# probe_v2.net
KiCad netlist of a schematic drawn in EAGLE
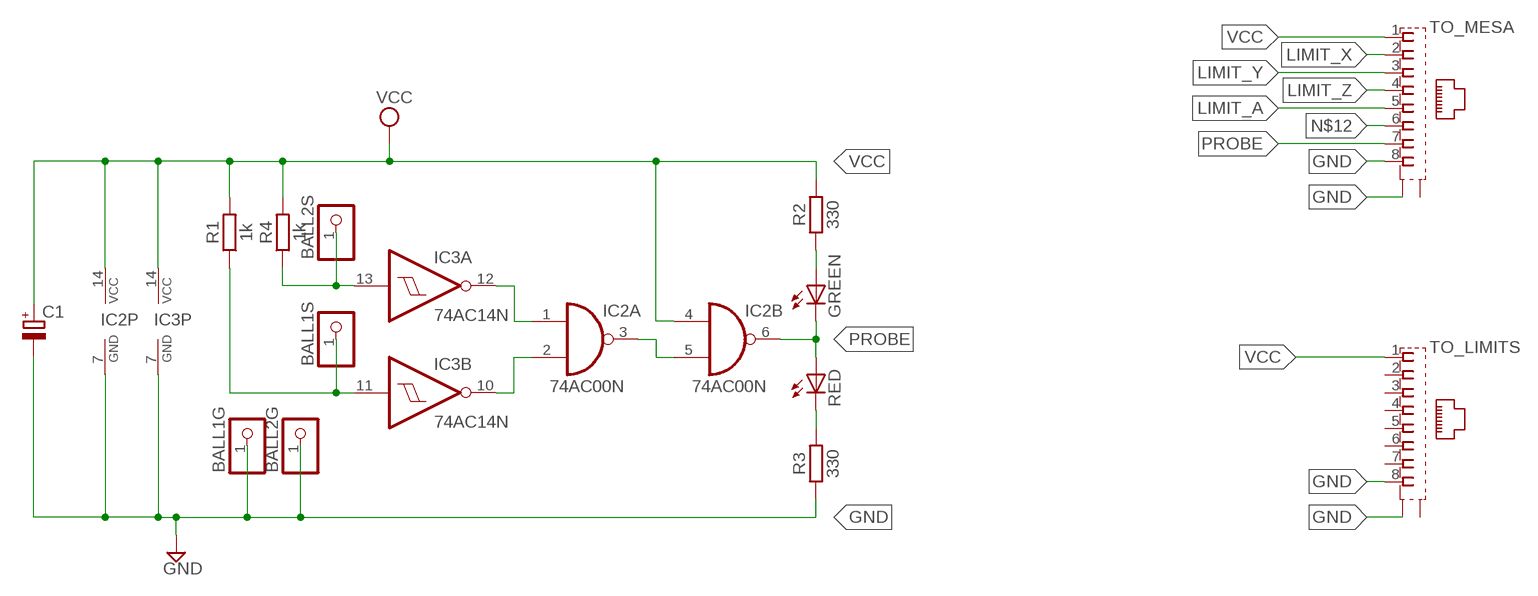
[diagram p0: schematic, sheet 1]

(export (version "E")
  (design (tool "Eeschema 10.0.6"))
  (components
    (comp (ref "BALL1G")
      (value "PINHD-1X1")
      (footprint "eagle-import:1X01")
      (libsource (lib "eagle-import") (part "PINHD-1X1"))
    )
    (comp (ref "BALL1S")
      (value "PINHD-1X1")
      (footprint "eagle-import:1X01")
      (libsource (lib "eagle-import") (part "PINHD-1X1"))
    )
    (comp (ref "BALL2G")
      (value "PINHD-1X1")
      (footprint "eagle-import:1X01")
      (libsource (lib "eagle-import") (part "PINHD-1X1"))
    )
    (comp (ref "BALL2S")
      (value "PINHD-1X1")
      (footprint "eagle-import:1X01")
      (libsource (lib "eagle-import") (part "PINHD-1X1"))
    )
    (comp (ref "C1")
      (value "CPOL-EUE5-10.5")
      (footprint "eagle-import:E5-10,5")
      (libsource (lib "eagle-import") (part "CPOL-EUE5-10.5"))
    )
    (comp (ref "GREEN")
      (value "LED5MM")
      (footprint "eagle-import:LED5MM")
      (libsource (lib "eagle-import") (part "LED5MM"))
    )
    (comp (ref "IC2")
      (value "74AC00N")
      (footprint "eagle-import:DIL14")
      (libsource (lib "eagle-import") (part "7400NAC"))
    )
    (comp (ref "IC3")
      (value "74AC14N")
      (footprint "eagle-import:DIL14")
      (libsource (lib "eagle-import") (part "7414NAC"))
    )
    (comp (ref "R1")
      (value "1k")
      (footprint "eagle-import:0207_10")
      (libsource (lib "eagle-import") (part "R-EU_0207/10"))
    )
    (comp (ref "R2")
      (value "330")
      (footprint "eagle-import:0207_10")
      (libsource (lib "eagle-import") (part "R-EU_0207/10"))
    )
    (comp (ref "R3")
      (value "330")
      (footprint "eagle-import:0207_10")
      (libsource (lib "eagle-import") (part "R-EU_0207/10"))
    )
    (comp (ref "R4")
      (value "1k")
      (footprint "eagle-import:0207_10")
      (libsource (lib "eagle-import") (part "R-EU_0207/10"))
    )
    (comp (ref "RED")
      (value "LED5MM")
      (footprint "eagle-import:LED5MM")
      (libsource (lib "eagle-import") (part "LED5MM"))
    )
    (comp (ref "TO_LIMITS")
      (value "558310-1")
      (footprint "eagle-import:558310-1")
      (libsource (lib "eagle-import") (part "558310-1"))
    )
    (comp (ref "TO_MESA")
      (value "558310-1")
      (footprint "eagle-import:558310-1")
      (libsource (lib "eagle-import") (part "558310-1"))
    )
  )
  (nets
    (net (code "1") (name "GND") (class "Default")
      (node (ref "BALL1G") (pin "1") (pinfunction "1_1") (pintype "passive"))
      (node (ref "BALL2G") (pin "1") (pinfunction "1_1") (pintype "passive"))
      (node (ref "C1") (pin "-") (pinfunction "-_-") (pintype "passive"))
      (node (ref "IC2") (pin "7") (pinfunction "GND_7") (pintype "power_in"))
      (node (ref "IC3") (pin "7") (pinfunction "GND_7") (pintype "power_in"))
      (node (ref "R3") (pin "1") (pinfunction "1_1") (pintype "passive"))
      (node (ref "TO_LIMITS") (pin "8") (pinfunction "8_8") (pintype "passive"))
      (node (ref "TO_LIMITS") (pin "G2") (pinfunction "S1_G2") (pintype "passive"))
      (node (ref "TO_MESA") (pin "8") (pinfunction "8_8") (pintype "passive"))
      (node (ref "TO_MESA") (pin "G2") (pinfunction "S1_G2") (pintype "passive"))
    )
    (net (code "2") (name "LIMIT_A") (class "Default")
      (node (ref "TO_MESA") (pin "5") (pinfunction "5_5") (pintype "passive"))
    )
    (net (code "3") (name "LIMIT_X") (class "Default")
      (node (ref "TO_MESA") (pin "2") (pinfunction "2_2") (pintype "passive"))
    )
    (net (code "4") (name "LIMIT_Y") (class "Default")
      (node (ref "TO_MESA") (pin "3") (pinfunction "3_3") (pintype "passive"))
    )
    (net (code "5") (name "LIMIT_Z") (class "Default")
      (node (ref "TO_MESA") (pin "4") (pinfunction "4_4") (pintype "passive"))
    )
    (net (code "6") (name "N$12") (class "Default")
      (node (ref "TO_MESA") (pin "6") (pinfunction "6_6") (pintype "passive"))
    )
    (net (code "7") (name "Net-(GREEN-PadA)") (class "Default")
      (node (ref "GREEN") (pin "A") (pinfunction "A_A") (pintype "passive"))
      (node (ref "R2") (pin "1") (pinfunction "1_1") (pintype "passive"))
    )
    (net (code "8") (name "Net-(IC2A-I0)") (class "Default")
      (node (ref "IC2") (pin "1") (pinfunction "I0_1") (pintype "input"))
      (node (ref "IC3") (pin "12") (pinfunction "O_12") (pintype "output"))
    )
    (net (code "9") (name "Net-(IC2A-I1)") (class "Default")
      (node (ref "IC2") (pin "2") (pinfunction "I1_2") (pintype "input"))
      (node (ref "IC3") (pin "10") (pinfunction "O_10") (pintype "output"))
    )
    (net (code "10") (name "Net-(IC2A-O)") (class "Default")
      (node (ref "IC2") (pin "3") (pinfunction "O_3") (pintype "output"))
      (node (ref "IC2") (pin "5") (pinfunction "I1_5") (pintype "input"))
    )
    (net (code "11") (name "Net-(IC3A-I)") (class "Default")
      (node (ref "BALL2S") (pin "1") (pinfunction "1_1") (pintype "passive"))
      (node (ref "IC3") (pin "13") (pinfunction "I_13") (pintype "input"))
      (node (ref "R4") (pin "1") (pinfunction "1_1") (pintype "passive"))
    )
    (net (code "12") (name "Net-(IC3B-I)") (class "Default")
      (node (ref "BALL1S") (pin "1") (pinfunction "1_1") (pintype "passive"))
      (node (ref "IC3") (pin "11") (pinfunction "I_11") (pintype "input"))
      (node (ref "R1") (pin "1") (pinfunction "1_1") (pintype "passive"))
    )
    (net (code "13") (name "Net-(RED-C)") (class "Default")
      (node (ref "R3") (pin "2") (pinfunction "2_2") (pintype "passive"))
      (node (ref "RED") (pin "K") (pinfunction "C_K") (pintype "passive"))
    )
    (net (code "14") (name "PROBE") (class "Default")
      (node (ref "GREEN") (pin "K") (pinfunction "C_K") (pintype "passive"))
      (node (ref "IC2") (pin "6") (pinfunction "O_6") (pintype "output"))
      (node (ref "RED") (pin "A") (pinfunction "A_A") (pintype "passive"))
      (node (ref "TO_MESA") (pin "7") (pinfunction "7_7") (pintype "passive"))
    )
    (net (code "15") (name "VCC") (class "Default")
      (node (ref "C1") (pin "+") (pinfunction "+_+") (pintype "passive"))
      (node (ref "IC2") (pin "14") (pinfunction "VCC_14") (pintype "power_in"))
      (node (ref "IC2") (pin "4") (pinfunction "I0_4") (pintype "input"))
      (node (ref "IC3") (pin "14") (pinfunction "VCC_14") (pintype "power_in"))
      (node (ref "R1") (pin "2") (pinfunction "2_2") (pintype "passive"))
      (node (ref "R2") (pin "2") (pinfunction "2_2") (pintype "passive"))
      (node (ref "R4") (pin "2") (pinfunction "2_2") (pintype "passive"))
      (node (ref "TO_LIMITS") (pin "1") (pinfunction "1_1") (pintype "passive"))
      (node (ref "TO_MESA") (pin "1") (pinfunction "1_1") (pintype "passive"))
    )
    (net (code "16") (name "unconnected-(TO_LIMITS-Pad2)") (class "Default")
      (node (ref "TO_LIMITS") (pin "2") (pinfunction "2_2") (pintype "passive"))
    )
    (net (code "17") (name "unconnected-(TO_LIMITS-Pad3)") (class "Default")
      (node (ref "TO_LIMITS") (pin "3") (pinfunction "3_3") (pintype "passive"))
    )
    (net (code "18") (name "unconnected-(TO_LIMITS-Pad4)") (class "Default")
      (node (ref "TO_LIMITS") (pin "4") (pinfunction "4_4") (pintype "passive"))
    )
    (net (code "19") (name "unconnected-(TO_LIMITS-Pad5)") (class "Default")
      (node (ref "TO_LIMITS") (pin "5") (pinfunction "5_5") (pintype "passive"))
    )
    (net (code "20") (name "unconnected-(TO_LIMITS-Pad6)") (class "Default")
      (node (ref "TO_LIMITS") (pin "6") (pinfunction "6_6") (pintype "passive"))
    )
    (net (code "21") (name "unconnected-(TO_LIMITS-Pad7)") (class "Default")
      (node (ref "TO_LIMITS") (pin "7") (pinfunction "7_7") (pintype "passive"))
    )
    (net (code "22") (name "unconnected-(TO_LIMITS-S2-PadG1)") (class "Default")
      (node (ref "TO_LIMITS") (pin "G1") (pinfunction "S2_G1") (pintype "passive"))
    )
    (net (code "23") (name "unconnected-(TO_MESA-S2-PadG1)") (class "Default")
      (node (ref "TO_MESA") (pin "G1") (pinfunction "S2_G1") (pintype "passive"))
    )
  )
)
